# FT2232HL_master.net
KiCad netlist of a schematic drawn in Altium Designer
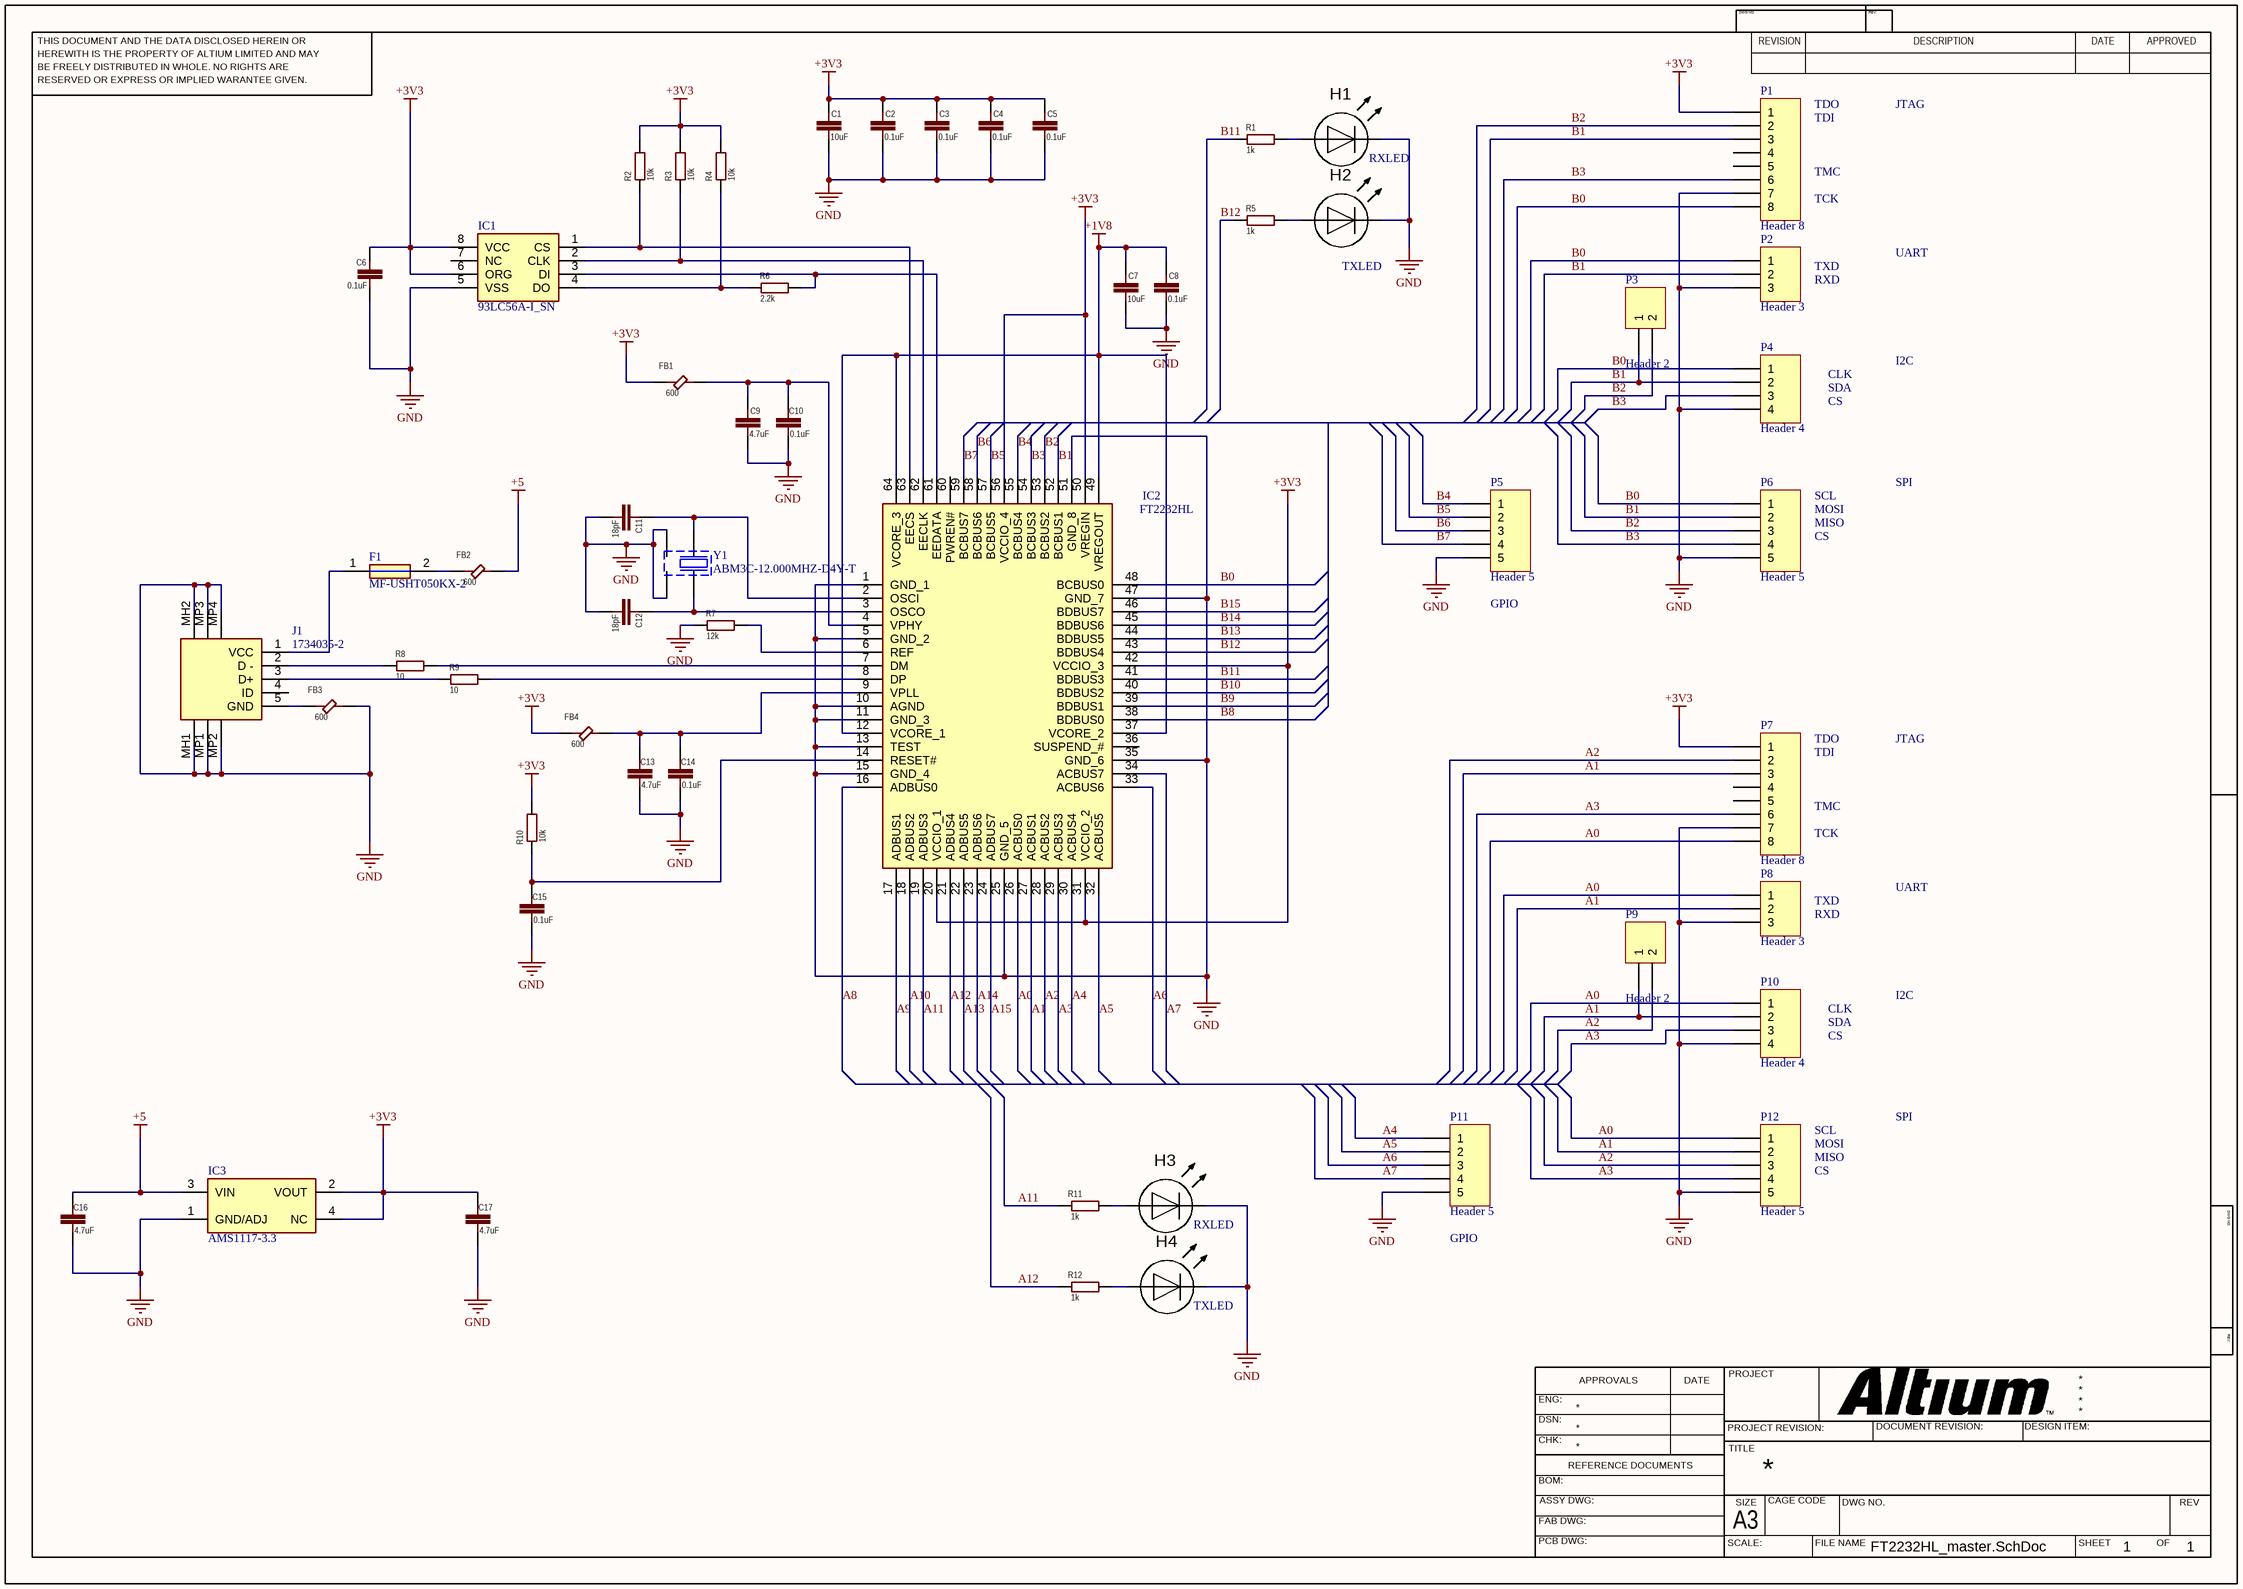
[diagram p0: FT2232HL_master.SchDoc]

(export (version "E")
  (design (tool "Eeschema 10.0.6"))
  (components
    (comp (ref "C1") (value "10uF") (footprint "C_0805") (libsource (lib "Passive") (part "C")))
    (comp (ref "C2") (value "0.1uF") (footprint "C_0603") (libsource (lib "Passive") (part "C")))
    (comp (ref "C3") (value "0.1uF") (footprint "C_0603") (libsource (lib "Passive") (part "C")))
    (comp (ref "C4") (value "0.1uF") (footprint "C_0603") (libsource (lib "Passive") (part "C")))
    (comp (ref "C5") (value "0.1uF") (footprint "C_0603") (libsource (lib "Passive") (part "C")))
    (comp (ref "C6") (value "0.1uF") (footprint "C_0603") (libsource (lib "") (part "C_1")))
    (comp (ref "C7") (value "10uF") (footprint "C_0805") (libsource (lib "Passive") (part "C")))
    (comp (ref "C8") (value "0.1uF") (footprint "C_0603") (libsource (lib "Passive") (part "C")))
    (comp (ref "C9") (value "4.7uF") (footprint "C_0603") (libsource (lib "Passive") (part "C")))
    (comp (ref "C10") (value "0.1uF") (footprint "C_0603") (libsource (lib "Passive") (part "C")))
    (comp (ref "C11") (value "18pF") (footprint "C_0603") (libsource (lib "") (part "C_1")))
    (comp (ref "C12") (value "18pF") (footprint "C_0603") (libsource (lib "") (part "C_1")))
    (comp (ref "C13") (value "4.7uF") (footprint "C_0603") (libsource (lib "Passive") (part "C")))
    (comp (ref "C14") (value "0.1uF") (footprint "C_0603") (libsource (lib "Passive") (part "C")))
    (comp (ref "C15") (value "0.1uF") (footprint "C_0603") (libsource (lib "Passive") (part "C")))
    (comp (ref "C16") (value "4.7uF") (footprint "C_0603") (libsource (lib "Passive") (part "C")))
    (comp (ref "C17") (value "4.7uF") (footprint "C_0603") (libsource (lib "Passive") (part "C")))
    (comp (ref "F1")
      (value "MF-USHT050KX-2")
      (footprint "SamacSys:FUSC3226X85N")
      (description "Fuse")
      (fields (field (name "MOUSER PART NUMBER") "652-MF-USHT050KX-2"))
      (libsource (lib "SamacSys") (part "MF-USHT050KX-2"))
    )
    (comp (ref "FB1")
      (value "600")
      (footprint "R_0603")
      (description "Ferrite Bead")
      (libsource (lib "Passive") (part "FB"))
    )
    (comp (ref "FB2")
      (value "600")
      (footprint "R_0805")
      (description "Ferrite Bead")
      (libsource (lib "Passive") (part "FB"))
    )
    (comp (ref "FB3")
      (value "600")
      (footprint "R_0805")
      (description "Ferrite Bead")
      (libsource (lib "Passive") (part "FB"))
    )
    (comp (ref "FB4")
      (value "600")
      (footprint "R_0603")
      (description "Ferrite Bead")
      (libsource (lib "Passive") (part "FB"))
    )
    (comp (ref "H1") (value "LED") (footprint "LED 0603_1608 GREEN") (libsource (lib "VD") (part "LED")))
    (comp (ref "H2") (value "LED") (footprint "LED 0603_1608 GREEN") (libsource (lib "VD") (part "LED")))
    (comp (ref "H3") (value "LED") (footprint "LED 0603_1608 GREEN") (libsource (lib "VD") (part "LED")))
    (comp (ref "H4") (value "LED") (footprint "LED 0603_1608 GREEN") (libsource (lib "VD") (part "LED")))
    (comp (ref "IC1")
      (value "93LC56A-I_SN")
      (footprint "SamacSys:SOIC127P600X175-8N")
      (description "Integrated Circuit")
      (fields
        (field (name "MANUFACTURER_PART_NUMBER") "93LC56A-I/SN")
        (field (name "MOUSER PART NUMBER") "579-93LC56A-I/SN")
      )
      (libsource (lib "*") (part "93LC56A-I_SN"))
    )
    (comp (ref "IC2")
      (value "FT2232HL")
      (footprint "SamacSys:QFP50P1200X1200X160-64N")
      (description "Integrated Circuit")
      (libsource (lib "*") (part "FT2232HL"))
    )
    (comp (ref "IC3")
      (value "AMS1117-3.3")
      (footprint "SamacSys:SOT229P700X180-4N")
      (description "LDO 3.3V")
      (libsource (lib "SamacSys") (part "AMS1117-3.3"))
    )
    (comp (ref "J1")
      (value "1734035-2")
      (footprint "SamacSys:17340352")
      (description "Connector")
      (fields (field (name "MOUSER PART NUMBER") "571-1734035-2"))
      (libsource (lib "SamacSys") (part "1734035-2"))
    )
    (comp (ref "P1")
      (value "Header 8")
      (footprint "HDR1X8")
      (description "Header, 8-Pin")
      (fields (field (name "PUBLISHER") "Altium Limited"))
      (libsource (lib "Miscellaneous Connectors") (part "Header 8"))
    )
    (comp (ref "P2")
      (value "Header 3")
      (footprint "HDR1X3")
      (description "Header, 3-Pin")
      (fields (field (name "PUBLISHER") "Altium Limited"))
      (libsource (lib "Miscellaneous Connectors") (part "Header 3"))
    )
    (comp (ref "P3")
      (value "Header 2")
      (footprint "HDR1X2")
      (description "Header, 2-Pin")
      (fields (field (name "PUBLISHER") "Altium Limited"))
      (libsource (lib "Miscellaneous Connectors") (part "Header 2"))
    )
    (comp (ref "P4")
      (value "Header 4")
      (footprint "HDR1X4")
      (description "Header, 4-Pin")
      (fields (field (name "PUBLISHER") "Altium Limited"))
      (libsource (lib "Miscellaneous Connectors") (part "Header 4"))
    )
    (comp (ref "P5")
      (value "Header 5")
      (footprint "HDR1X5")
      (description "Header, 5-Pin")
      (fields (field (name "PUBLISHER") "Altium Limited"))
      (libsource (lib "Miscellaneous Connectors") (part "Header 5"))
    )
    (comp (ref "P6")
      (value "Header 5")
      (footprint "HDR1X5")
      (description "Header, 5-Pin")
      (fields (field (name "PUBLISHER") "Altium Limited"))
      (libsource (lib "Miscellaneous Connectors") (part "Header 5"))
    )
    (comp (ref "P7")
      (value "Header 8")
      (footprint "HDR1X8")
      (description "Header, 8-Pin")
      (fields (field (name "PUBLISHER") "Altium Limited"))
      (libsource (lib "Miscellaneous Connectors") (part "Header 8"))
    )
    (comp (ref "P8")
      (value "Header 3")
      (footprint "HDR1X3")
      (description "Header, 3-Pin")
      (fields (field (name "PUBLISHER") "Altium Limited"))
      (libsource (lib "Miscellaneous Connectors") (part "Header 3"))
    )
    (comp (ref "P9")
      (value "Header 2")
      (footprint "HDR1X2")
      (description "Header, 2-Pin")
      (fields (field (name "PUBLISHER") "Altium Limited"))
      (libsource (lib "Miscellaneous Connectors") (part "Header 2"))
    )
    (comp (ref "P10")
      (value "Header 4")
      (footprint "HDR1X4")
      (description "Header, 4-Pin")
      (fields (field (name "PUBLISHER") "Altium Limited"))
      (libsource (lib "Miscellaneous Connectors") (part "Header 4"))
    )
    (comp (ref "P11")
      (value "Header 5")
      (footprint "HDR1X5")
      (description "Header, 5-Pin")
      (fields (field (name "PUBLISHER") "Altium Limited"))
      (libsource (lib "Miscellaneous Connectors") (part "Header 5"))
    )
    (comp (ref "P12")
      (value "Header 5")
      (footprint "HDR1X5")
      (description "Header, 5-Pin")
      (fields (field (name "PUBLISHER") "Altium Limited"))
      (libsource (lib "Miscellaneous Connectors") (part "Header 5"))
    )
    (comp (ref "R1") (value "1k") (footprint "R_0603") (libsource (lib "Passive") (part "R")))
    (comp (ref "R2") (value "10k") (footprint "R_0603") (libsource (lib "Passive") (part "R")))
    (comp (ref "R3") (value "10k") (footprint "R_0603") (libsource (lib "Passive") (part "R")))
    (comp (ref "R4") (value "10k") (footprint "R_0603") (libsource (lib "Passive") (part "R")))
    (comp (ref "R5") (value "1k") (footprint "R_0603") (libsource (lib "Passive") (part "R")))
    (comp (ref "R6") (value "2.2k") (footprint "R_0603") (libsource (lib "Passive") (part "R")))
    (comp (ref "R7") (value "12k") (footprint "R_0603") (libsource (lib "Passive") (part "R")))
    (comp (ref "R8") (value "10") (footprint "R_0603") (libsource (lib "Passive") (part "R")))
    (comp (ref "R9") (value "10") (footprint "R_0603") (libsource (lib "Passive") (part "R")))
    (comp (ref "R10") (value "10k") (footprint "R_0603") (libsource (lib "Passive") (part "R")))
    (comp (ref "R11") (value "1k") (footprint "R_0603") (libsource (lib "Passive") (part "R")))
    (comp (ref "R12") (value "1k") (footprint "R_0603") (libsource (lib "Passive") (part "R")))
    (comp (ref "Y1")
      (value "ABM3C-12.000MHZ-D4Y-T")
      (footprint "ABM3C10000MHZD4YT")
      (description "Crystal or Oscillator")
      (fields
        (field (name "MANUFACTURER_PART_NUMBER") "ABM3C-10.000MHZ-D4Y-T")
        (field (name "MOUSER PART NUMBER") "815-ABM3C-10-D4YT")
      )
      (libsource (lib "SamacSys") (part "ABM3C-10.000MHZ-D4Y-T"))
    )
  )
  (nets
    (net (code "1") (name "+1V8") (class "Default")
      (node (ref "C7") (pin "2") (pinfunction "2_2") (pintype "passive"))
      (node (ref "C8") (pin "2") (pinfunction "2_2") (pintype "passive"))
      (node (ref "IC2") (pin "12") (pinfunction "VCORE_1_12") (pintype "passive"))
      (node (ref "IC2") (pin "37") (pinfunction "VCORE_2_37") (pintype "passive"))
      (node (ref "IC2") (pin "49") (pinfunction "VREGOUT_49") (pintype "passive"))
      (node (ref "IC2") (pin "64") (pinfunction "VCORE_3_64") (pintype "passive"))
    )
    (net (code "2") (name "+3V3") (class "Default")
      (node (ref "C1") (pin "2") (pinfunction "2_2") (pintype "passive"))
      (node (ref "C17") (pin "2") (pinfunction "2_2") (pintype "passive"))
      (node (ref "C2") (pin "2") (pinfunction "2_2") (pintype "passive"))
      (node (ref "C3") (pin "2") (pinfunction "2_2") (pintype "passive"))
      (node (ref "C4") (pin "2") (pinfunction "2_2") (pintype "passive"))
      (node (ref "C5") (pin "2") (pinfunction "2_2") (pintype "passive"))
      (node (ref "C6") (pin "2") (pinfunction "2_2") (pintype "passive"))
      (node (ref "FB1") (pin "1") (pinfunction "1_1") (pintype "passive"))
      (node (ref "FB4") (pin "1") (pinfunction "1_1") (pintype "passive"))
      (node (ref "IC1") (pin "6") (pinfunction "ORG_6") (pintype "passive"))
      (node (ref "IC1") (pin "8") (pinfunction "VCC_8") (pintype "passive"))
      (node (ref "IC2") (pin "20") (pinfunction "VCCIO_1_20") (pintype "passive"))
      (node (ref "IC2") (pin "31") (pinfunction "VCCIO_2_31") (pintype "passive"))
      (node (ref "IC2") (pin "42") (pinfunction "VCCIO_3_42") (pintype "passive"))
      (node (ref "IC2") (pin "50") (pinfunction "VREGIN_50") (pintype "passive"))
      (node (ref "IC2") (pin "56") (pinfunction "VCCIO_4_56") (pintype "passive"))
      (node (ref "IC3") (pin "2") (pinfunction "VOUT_2") (pintype "passive"))
      (node (ref "IC3") (pin "4") (pinfunction "NC_4") (pintype "passive"))
      (node (ref "P1") (pin "1") (pinfunction "1_1") (pintype "passive"))
      (node (ref "P7") (pin "1") (pinfunction "1_1") (pintype "passive"))
      (node (ref "R10") (pin "2") (pinfunction "2_2") (pintype "passive"))
      (node (ref "R2") (pin "2") (pinfunction "2_2") (pintype "passive"))
      (node (ref "R3") (pin "2") (pinfunction "2_2") (pintype "passive"))
      (node (ref "R4") (pin "2") (pinfunction "2_2") (pintype "passive"))
    )
    (net (code "3") (name "+5") (class "Default")
      (node (ref "C16") (pin "2") (pinfunction "2_2") (pintype "passive"))
      (node (ref "FB2") (pin "2") (pinfunction "2_2") (pintype "passive"))
      (node (ref "IC3") (pin "3") (pinfunction "VIN_3") (pintype "passive"))
    )
    (net (code "4") (name "/A0") (class "Default")
      (node (ref "IC2") (pin "26") (pinfunction "ACBUS0_26") (pintype "passive"))
      (node (ref "P10") (pin "1") (pinfunction "1_1") (pintype "passive"))
      (node (ref "P12") (pin "1") (pinfunction "1_1") (pintype "passive"))
      (node (ref "P7") (pin "8") (pinfunction "8_8") (pintype "passive"))
      (node (ref "P8") (pin "1") (pinfunction "1_1") (pintype "passive"))
    )
    (net (code "5") (name "/A1") (class "Default")
      (node (ref "IC2") (pin "27") (pinfunction "ACBUS1_27") (pintype "passive"))
      (node (ref "P10") (pin "2") (pinfunction "2_2") (pintype "passive"))
      (node (ref "P12") (pin "2") (pinfunction "2_2") (pintype "passive"))
      (node (ref "P7") (pin "3") (pinfunction "3_3") (pintype "passive"))
      (node (ref "P8") (pin "2") (pinfunction "2_2") (pintype "passive"))
      (node (ref "P9") (pin "1") (pinfunction "1_1") (pintype "passive"))
    )
    (net (code "6") (name "/A2") (class "Default")
      (node (ref "IC2") (pin "28") (pinfunction "ACBUS2_28") (pintype "passive"))
      (node (ref "P12") (pin "3") (pinfunction "3_3") (pintype "passive"))
      (node (ref "P7") (pin "2") (pinfunction "2_2") (pintype "passive"))
      (node (ref "P9") (pin "2") (pinfunction "2_2") (pintype "passive"))
    )
    (net (code "7") (name "/A3") (class "Default")
      (node (ref "IC2") (pin "29") (pinfunction "ACBUS3_29") (pintype "passive"))
      (node (ref "P10") (pin "3") (pinfunction "3_3") (pintype "passive"))
      (node (ref "P12") (pin "4") (pinfunction "4_4") (pintype "passive"))
      (node (ref "P7") (pin "6") (pinfunction "6_6") (pintype "passive"))
    )
    (net (code "8") (name "/A4") (class "Default")
      (node (ref "IC2") (pin "30") (pinfunction "ACBUS4_30") (pintype "passive"))
      (node (ref "P11") (pin "1") (pinfunction "1_1") (pintype "passive"))
    )
    (net (code "9") (name "/A5") (class "Default")
      (node (ref "IC2") (pin "32") (pinfunction "ACBUS5_32") (pintype "passive"))
      (node (ref "P11") (pin "2") (pinfunction "2_2") (pintype "passive"))
    )
    (net (code "10") (name "/A6") (class "Default")
      (node (ref "IC2") (pin "33") (pinfunction "ACBUS6_33") (pintype "passive"))
      (node (ref "P11") (pin "3") (pinfunction "3_3") (pintype "passive"))
    )
    (net (code "11") (name "/A7") (class "Default")
      (node (ref "IC2") (pin "34") (pinfunction "ACBUS7_34") (pintype "passive"))
      (node (ref "P11") (pin "4") (pinfunction "4_4") (pintype "passive"))
    )
    (net (code "12") (name "/A8") (class "Default")
      (node (ref "IC2") (pin "16") (pinfunction "ADBUS0_16") (pintype "passive"))
    )
    (net (code "13") (name "/A9") (class "Default")
      (node (ref "IC2") (pin "17") (pinfunction "ADBUS1_17") (pintype "passive"))
    )
    (net (code "14") (name "/A10") (class "Default")
      (node (ref "IC2") (pin "18") (pinfunction "ADBUS2_18") (pintype "passive"))
    )
    (net (code "15") (name "/A11") (class "Default")
      (node (ref "IC2") (pin "19") (pinfunction "ADBUS3_19") (pintype "passive"))
      (node (ref "R11") (pin "1") (pinfunction "1_1") (pintype "passive"))
    )
    (net (code "16") (name "/A12") (class "Default")
      (node (ref "IC2") (pin "21") (pinfunction "ADBUS4_21") (pintype "passive"))
      (node (ref "R12") (pin "1") (pinfunction "1_1") (pintype "passive"))
    )
    (net (code "17") (name "/A13") (class "Default")
      (node (ref "IC2") (pin "22") (pinfunction "ADBUS5_22") (pintype "passive"))
    )
    (net (code "18") (name "/A14") (class "Default")
      (node (ref "IC2") (pin "23") (pinfunction "ADBUS6_23") (pintype "passive"))
    )
    (net (code "19") (name "/A15") (class "Default")
      (node (ref "IC2") (pin "24") (pinfunction "ADBUS7_24") (pintype "passive"))
    )
    (net (code "20") (name "/B0") (class "Default")
      (node (ref "IC2") (pin "48") (pinfunction "BCBUS0_48") (pintype "passive"))
      (node (ref "P1") (pin "8") (pinfunction "8_8") (pintype "passive"))
      (node (ref "P2") (pin "1") (pinfunction "1_1") (pintype "passive"))
      (node (ref "P4") (pin "1") (pinfunction "1_1") (pintype "passive"))
      (node (ref "P6") (pin "1") (pinfunction "1_1") (pintype "passive"))
    )
    (net (code "21") (name "/B1") (class "Default")
      (node (ref "IC2") (pin "52") (pinfunction "BCBUS1_52") (pintype "passive"))
      (node (ref "P1") (pin "3") (pinfunction "3_3") (pintype "passive"))
      (node (ref "P2") (pin "2") (pinfunction "2_2") (pintype "passive"))
      (node (ref "P3") (pin "1") (pinfunction "1_1") (pintype "passive"))
      (node (ref "P4") (pin "2") (pinfunction "2_2") (pintype "passive"))
      (node (ref "P6") (pin "2") (pinfunction "2_2") (pintype "passive"))
    )
    (net (code "22") (name "/B2") (class "Default")
      (node (ref "IC2") (pin "53") (pinfunction "BCBUS2_53") (pintype "passive"))
      (node (ref "P1") (pin "2") (pinfunction "2_2") (pintype "passive"))
      (node (ref "P3") (pin "2") (pinfunction "2_2") (pintype "passive"))
      (node (ref "P6") (pin "3") (pinfunction "3_3") (pintype "passive"))
    )
    (net (code "23") (name "/B3") (class "Default")
      (node (ref "IC2") (pin "54") (pinfunction "BCBUS3_54") (pintype "passive"))
      (node (ref "P1") (pin "6") (pinfunction "6_6") (pintype "passive"))
      (node (ref "P4") (pin "3") (pinfunction "3_3") (pintype "passive"))
      (node (ref "P6") (pin "4") (pinfunction "4_4") (pintype "passive"))
    )
    (net (code "24") (name "/B4") (class "Default")
      (node (ref "IC2") (pin "55") (pinfunction "BCBUS4_55") (pintype "passive"))
      (node (ref "P5") (pin "1") (pinfunction "1_1") (pintype "passive"))
    )
    (net (code "25") (name "/B5") (class "Default")
      (node (ref "IC2") (pin "57") (pinfunction "BCBUS5_57") (pintype "passive"))
      (node (ref "P5") (pin "2") (pinfunction "2_2") (pintype "passive"))
    )
    (net (code "26") (name "/B6") (class "Default")
      (node (ref "IC2") (pin "58") (pinfunction "BCBUS6_58") (pintype "passive"))
      (node (ref "P5") (pin "3") (pinfunction "3_3") (pintype "passive"))
    )
    (net (code "27") (name "/B7") (class "Default")
      (node (ref "IC2") (pin "59") (pinfunction "BCBUS7_59") (pintype "passive"))
      (node (ref "P5") (pin "4") (pinfunction "4_4") (pintype "passive"))
    )
    (net (code "28") (name "/B8") (class "Default")
      (node (ref "IC2") (pin "38") (pinfunction "BDBUS0_38") (pintype "passive"))
    )
    (net (code "29") (name "/B9") (class "Default")
      (node (ref "IC2") (pin "39") (pinfunction "BDBUS1_39") (pintype "passive"))
    )
    (net (code "30") (name "/B10") (class "Default")
      (node (ref "IC2") (pin "40") (pinfunction "BDBUS2_40") (pintype "passive"))
    )
    (net (code "31") (name "/B11") (class "Default")
      (node (ref "IC2") (pin "41") (pinfunction "BDBUS3_41") (pintype "passive"))
      (node (ref "R1") (pin "1") (pinfunction "1_1") (pintype "passive"))
    )
    (net (code "32") (name "/B12") (class "Default")
      (node (ref "IC2") (pin "43") (pinfunction "BDBUS4_43") (pintype "passive"))
      (node (ref "R5") (pin "1") (pinfunction "1_1") (pintype "passive"))
    )
    (net (code "33") (name "/B13") (class "Default")
      (node (ref "IC2") (pin "44") (pinfunction "BDBUS5_44") (pintype "passive"))
    )
    (net (code "34") (name "/B14") (class "Default")
      (node (ref "IC2") (pin "45") (pinfunction "BDBUS6_45") (pintype "passive"))
    )
    (net (code "35") (name "/B15") (class "Default")
      (node (ref "IC2") (pin "46") (pinfunction "BDBUS7_46") (pintype "passive"))
    )
    (net (code "36") (name "GND") (class "Default")
      (node (ref "C1") (pin "1") (pinfunction "1_1") (pintype "passive"))
      (node (ref "C10") (pin "1") (pinfunction "1_1") (pintype "passive"))
      (node (ref "C11") (pin "1") (pinfunction "1_1") (pintype "passive"))
      (node (ref "C12") (pin "1") (pinfunction "1_1") (pintype "passive"))
      (node (ref "C13") (pin "1") (pinfunction "1_1") (pintype "passive"))
      (node (ref "C14") (pin "1") (pinfunction "1_1") (pintype "passive"))
      (node (ref "C15") (pin "1") (pinfunction "1_1") (pintype "passive"))
      (node (ref "C16") (pin "1") (pinfunction "1_1") (pintype "passive"))
      (node (ref "C17") (pin "1") (pinfunction "1_1") (pintype "passive"))
      (node (ref "C2") (pin "1") (pinfunction "1_1") (pintype "passive"))
      (node (ref "C3") (pin "1") (pinfunction "1_1") (pintype "passive"))
      (node (ref "C4") (pin "1") (pinfunction "1_1") (pintype "passive"))
      (node (ref "C5") (pin "1") (pinfunction "1_1") (pintype "passive"))
      (node (ref "C6") (pin "1") (pinfunction "1_1") (pintype "passive"))
      (node (ref "C7") (pin "1") (pinfunction "1_1") (pintype "passive"))
      (node (ref "C8") (pin "1") (pinfunction "1_1") (pintype "passive"))
      (node (ref "C9") (pin "1") (pinfunction "1_1") (pintype "passive"))
      (node (ref "FB3") (pin "2") (pinfunction "2_2") (pintype "passive"))
      (node (ref "H1") (pin "2") (pinfunction "C_2") (pintype "passive"))
      (node (ref "H2") (pin "2") (pinfunction "C_2") (pintype "passive"))
      (node (ref "H3") (pin "2") (pinfunction "C_2") (pintype "passive"))
      (node (ref "H4") (pin "2") (pinfunction "C_2") (pintype "passive"))
      (node (ref "IC1") (pin "5") (pinfunction "VSS_5") (pintype "passive"))
      (node (ref "IC2") (pin "1") (pinfunction "GND_1_1") (pintype "passive"))
      (node (ref "IC2") (pin "10") (pinfunction "AGND_10") (pintype "passive"))
      (node (ref "IC2") (pin "11") (pinfunction "GND_3_11") (pintype "passive"))
      (node (ref "IC2") (pin "13") (pinfunction "TEST_13") (pintype "passive"))
      (node (ref "IC2") (pin "15") (pinfunction "GND_4_15") (pintype "passive"))
      (node (ref "IC2") (pin "25") (pinfunction "GND_5_25") (pintype "passive"))
      (node (ref "IC2") (pin "35") (pinfunction "GND_6_35") (pintype "passive"))
      (node (ref "IC2") (pin "47") (pinfunction "GND_7_47") (pintype "passive"))
      (node (ref "IC2") (pin "5") (pinfunction "GND_2_5") (pintype "passive"))
      (node (ref "IC2") (pin "51") (pinfunction "GND_8_51") (pintype "passive"))
      (node (ref "IC3") (pin "1") (pinfunction "GND/ADJ_1") (pintype "passive"))
      (node (ref "J1") (pin "MH1") (pinfunction "MH1_MH1") (pintype "passive"))
      (node (ref "J1") (pin "MH2") (pinfunction "MH2_MH2") (pintype "passive"))
      (node (ref "J1") (pin "MP1") (pinfunction "MP1_MP1") (pintype "passive"))
      (node (ref "J1") (pin "MP2") (pinfunction "MP2_MP2") (pintype "passive"))
      (node (ref "J1") (pin "MP3") (pinfunction "MP3_MP3") (pintype "passive"))
      (node (ref "J1") (pin "MP4") (pinfunction "MP4_MP4") (pintype "passive"))
      (node (ref "P1") (pin "7") (pinfunction "7_7") (pintype "passive"))
      (node (ref "P10") (pin "4") (pinfunction "4_4") (pintype "passive"))
      (node (ref "P11") (pin "5") (pinfunction "5_5") (pintype "passive"))
      (node (ref "P12") (pin "5") (pinfunction "5_5") (pintype "passive"))
      (node (ref "P2") (pin "3") (pinfunction "3_3") (pintype "passive"))
      (node (ref "P4") (pin "4") (pinfunction "4_4") (pintype "passive"))
      (node (ref "P5") (pin "5") (pinfunction "5_5") (pintype "passive"))
      (node (ref "P6") (pin "5") (pinfunction "5_5") (pintype "passive"))
      (node (ref "P7") (pin "7") (pinfunction "7_7") (pintype "passive"))
      (node (ref "P8") (pin "3") (pinfunction "3_3") (pintype "passive"))
      (node (ref "R7") (pin "1") (pinfunction "1_1") (pintype "passive"))
      (node (ref "Y1") (pin "2") (pinfunction "GND_1_2") (pintype "passive"))
      (node (ref "Y1") (pin "4") (pinfunction "GND_2_4") (pintype "passive"))
    )
    (net (code "37") (name "Net-(F1-Pad2)") (class "Default")
      (node (ref "F1") (pin "2") (pinfunction "2_2") (pintype "passive"))
      (node (ref "FB2") (pin "1") (pinfunction "1_1") (pintype "passive"))
    )
    (net (code "38") (name "Net-(H1-A)") (class "Default")
      (node (ref "H1") (pin "1") (pinfunction "A_1") (pintype "passive"))
      (node (ref "R1") (pin "2") (pinfunction "2_2") (pintype "passive"))
    )
    (net (code "39") (name "Net-(H2-A)") (class "Default")
      (node (ref "H2") (pin "1") (pinfunction "A_1") (pintype "passive"))
      (node (ref "R5") (pin "2") (pinfunction "2_2") (pintype "passive"))
    )
    (net (code "40") (name "Net-(H3-A)") (class "Default")
      (node (ref "H3") (pin "1") (pinfunction "A_1") (pintype "passive"))
      (node (ref "R11") (pin "2") (pinfunction "2_2") (pintype "passive"))
    )
    (net (code "41") (name "Net-(H4-A)") (class "Default")
      (node (ref "H4") (pin "1") (pinfunction "A_1") (pintype "passive"))
      (node (ref "R12") (pin "2") (pinfunction "2_2") (pintype "passive"))
    )
    (net (code "42") (name "Net-(IC1-CLK)") (class "Default")
      (node (ref "IC1") (pin "2") (pinfunction "CLK_2") (pintype "passive"))
      (node (ref "IC2") (pin "62") (pinfunction "EECLK_62") (pintype "passive"))
      (node (ref "R3") (pin "1") (pinfunction "1_1") (pintype "passive"))
    )
    (net (code "43") (name "Net-(IC1-CS)") (class "Default")
      (node (ref "IC1") (pin "1") (pinfunction "CS_1") (pintype "passive"))
      (node (ref "IC2") (pin "63") (pinfunction "EECS_63") (pintype "passive"))
      (node (ref "R2") (pin "1") (pinfunction "1_1") (pintype "passive"))
    )
    (net (code "44") (name "Net-(IC1-DI)") (class "Default")
      (node (ref "IC1") (pin "3") (pinfunction "DI_3") (pintype "passive"))
      (node (ref "IC2") (pin "61") (pinfunction "EEDATA_61") (pintype "passive"))
      (node (ref "R6") (pin "2") (pinfunction "2_2") (pintype "passive"))
    )
    (net (code "45") (name "Net-(IC1-DO)") (class "Default")
      (node (ref "IC1") (pin "4") (pinfunction "DO_4") (pintype "passive"))
      (node (ref "R4") (pin "1") (pinfunction "1_1") (pintype "passive"))
      (node (ref "R6") (pin "1") (pinfunction "1_1") (pintype "passive"))
    )
    (net (code "46") (name "Net-(IC2-DM)") (class "Default")
      (node (ref "IC2") (pin "7") (pinfunction "DM_7") (pintype "passive"))
      (node (ref "R8") (pin "2") (pinfunction "2_2") (pintype "passive"))
    )
    (net (code "47") (name "Net-(IC2-DP)") (class "Default")
      (node (ref "IC2") (pin "8") (pinfunction "DP_8") (pintype "passive"))
      (node (ref "R9") (pin "2") (pinfunction "2_2") (pintype "passive"))
    )
    (net (code "48") (name "Net-(IC2-OSCI)") (class "Default")
      (node (ref "C11") (pin "2") (pinfunction "2_2") (pintype "passive"))
      (node (ref "IC2") (pin "2") (pinfunction "OSCI_2") (pintype "passive"))
      (node (ref "Y1") (pin "1") (pinfunction "CRYSTAL_1_1") (pintype "passive"))
    )
    (net (code "49") (name "Net-(IC2-OSCO)") (class "Default")
      (node (ref "C12") (pin "2") (pinfunction "2_2") (pintype "passive"))
      (node (ref "IC2") (pin "3") (pinfunction "OSCO_3") (pintype "passive"))
      (node (ref "Y1") (pin "3") (pinfunction "CRYSTAL_2_3") (pintype "passive"))
    )
    (net (code "50") (name "Net-(IC2-REF)") (class "Default")
      (node (ref "IC2") (pin "6") (pinfunction "REF_6") (pintype "passive"))
      (node (ref "R7") (pin "2") (pinfunction "2_2") (pintype "passive"))
    )
    (net (code "51") (name "Net-(IC2-RESET#)") (class "Default")
      (node (ref "C15") (pin "2") (pinfunction "2_2") (pintype "passive"))
      (node (ref "IC2") (pin "14") (pinfunction "RESET#_14") (pintype "passive"))
      (node (ref "R10") (pin "1") (pinfunction "1_1") (pintype "passive"))
    )
    (net (code "52") (name "Net-(IC2-VPHY)") (class "Default")
      (node (ref "C10") (pin "2") (pinfunction "2_2") (pintype "passive"))
      (node (ref "C9") (pin "2") (pinfunction "2_2") (pintype "passive"))
      (node (ref "FB1") (pin "2") (pinfunction "2_2") (pintype "passive"))
      (node (ref "IC2") (pin "4") (pinfunction "VPHY_4") (pintype "passive"))
    )
    (net (code "53") (name "Net-(IC2-VPLL)") (class "Default")
      (node (ref "C13") (pin "2") (pinfunction "2_2") (pintype "passive"))
      (node (ref "C14") (pin "2") (pinfunction "2_2") (pintype "passive"))
      (node (ref "FB4") (pin "2") (pinfunction "2_2") (pintype "passive"))
      (node (ref "IC2") (pin "9") (pinfunction "VPLL_9") (pintype "passive"))
    )
    (net (code "54") (name "Net-(J1-D+)") (class "Default")
      (node (ref "J1") (pin "3") (pinfunction "D+_3") (pintype "passive"))
      (node (ref "R9") (pin "1") (pinfunction "1_1") (pintype "passive"))
    )
    (net (code "55") (name "Net-(J1-D_-)") (class "Default")
      (node (ref "J1") (pin "2") (pinfunction "D_-_2") (pintype "passive"))
      (node (ref "R8") (pin "1") (pinfunction "1_1") (pintype "passive"))
    )
    (net (code "56") (name "Net-(J1-GND)") (class "Default")
      (node (ref "FB3") (pin "1") (pinfunction "1_1") (pintype "passive"))
      (node (ref "J1") (pin "5") (pinfunction "GND_5") (pintype "passive"))
    )
    (net (code "57") (name "Net-(J1-VCC)") (class "Default")
      (node (ref "F1") (pin "1") (pinfunction "1_1") (pintype "passive"))
      (node (ref "J1") (pin "1") (pinfunction "VCC_1") (pintype "passive"))
    )
    (net (code "58") (name "unconnected-(IC1-NC-Pad7)") (class "Default")
      (node (ref "IC1") (pin "7") (pinfunction "NC_7") (pintype "passive"))
    )
    (net (code "59") (name "unconnected-(IC2-PWREN#-Pad60)") (class "Default")
      (node (ref "IC2") (pin "60") (pinfunction "PWREN#_60") (pintype "passive"))
    )
    (net (code "60") (name "unconnected-(IC2-SUSPEND_#-Pad36)") (class "Default")
      (node (ref "IC2") (pin "36") (pinfunction "SUSPEND_#_36") (pintype "passive"))
    )
    (net (code "61") (name "unconnected-(J1-ID-Pad4)") (class "Default")
      (node (ref "J1") (pin "4") (pinfunction "ID_4") (pintype "passive"))
    )
    (net (code "62") (name "unconnected-(P1-Pad4)") (class "Default")
      (node (ref "P1") (pin "4") (pinfunction "4_4") (pintype "passive"))
    )
    (net (code "63") (name "unconnected-(P1-Pad5)") (class "Default")
      (node (ref "P1") (pin "5") (pinfunction "5_5") (pintype "passive"))
    )
    (net (code "64") (name "unconnected-(P7-Pad4)") (class "Default")
      (node (ref "P7") (pin "4") (pinfunction "4_4") (pintype "passive"))
    )
    (net (code "65") (name "unconnected-(P7-Pad5)") (class "Default")
      (node (ref "P7") (pin "5") (pinfunction "5_5") (pintype "passive"))
    )
  )
)
